# bh_carrier_0_alph.net
KiCad netlist of a schematic drawn in Altium Designer
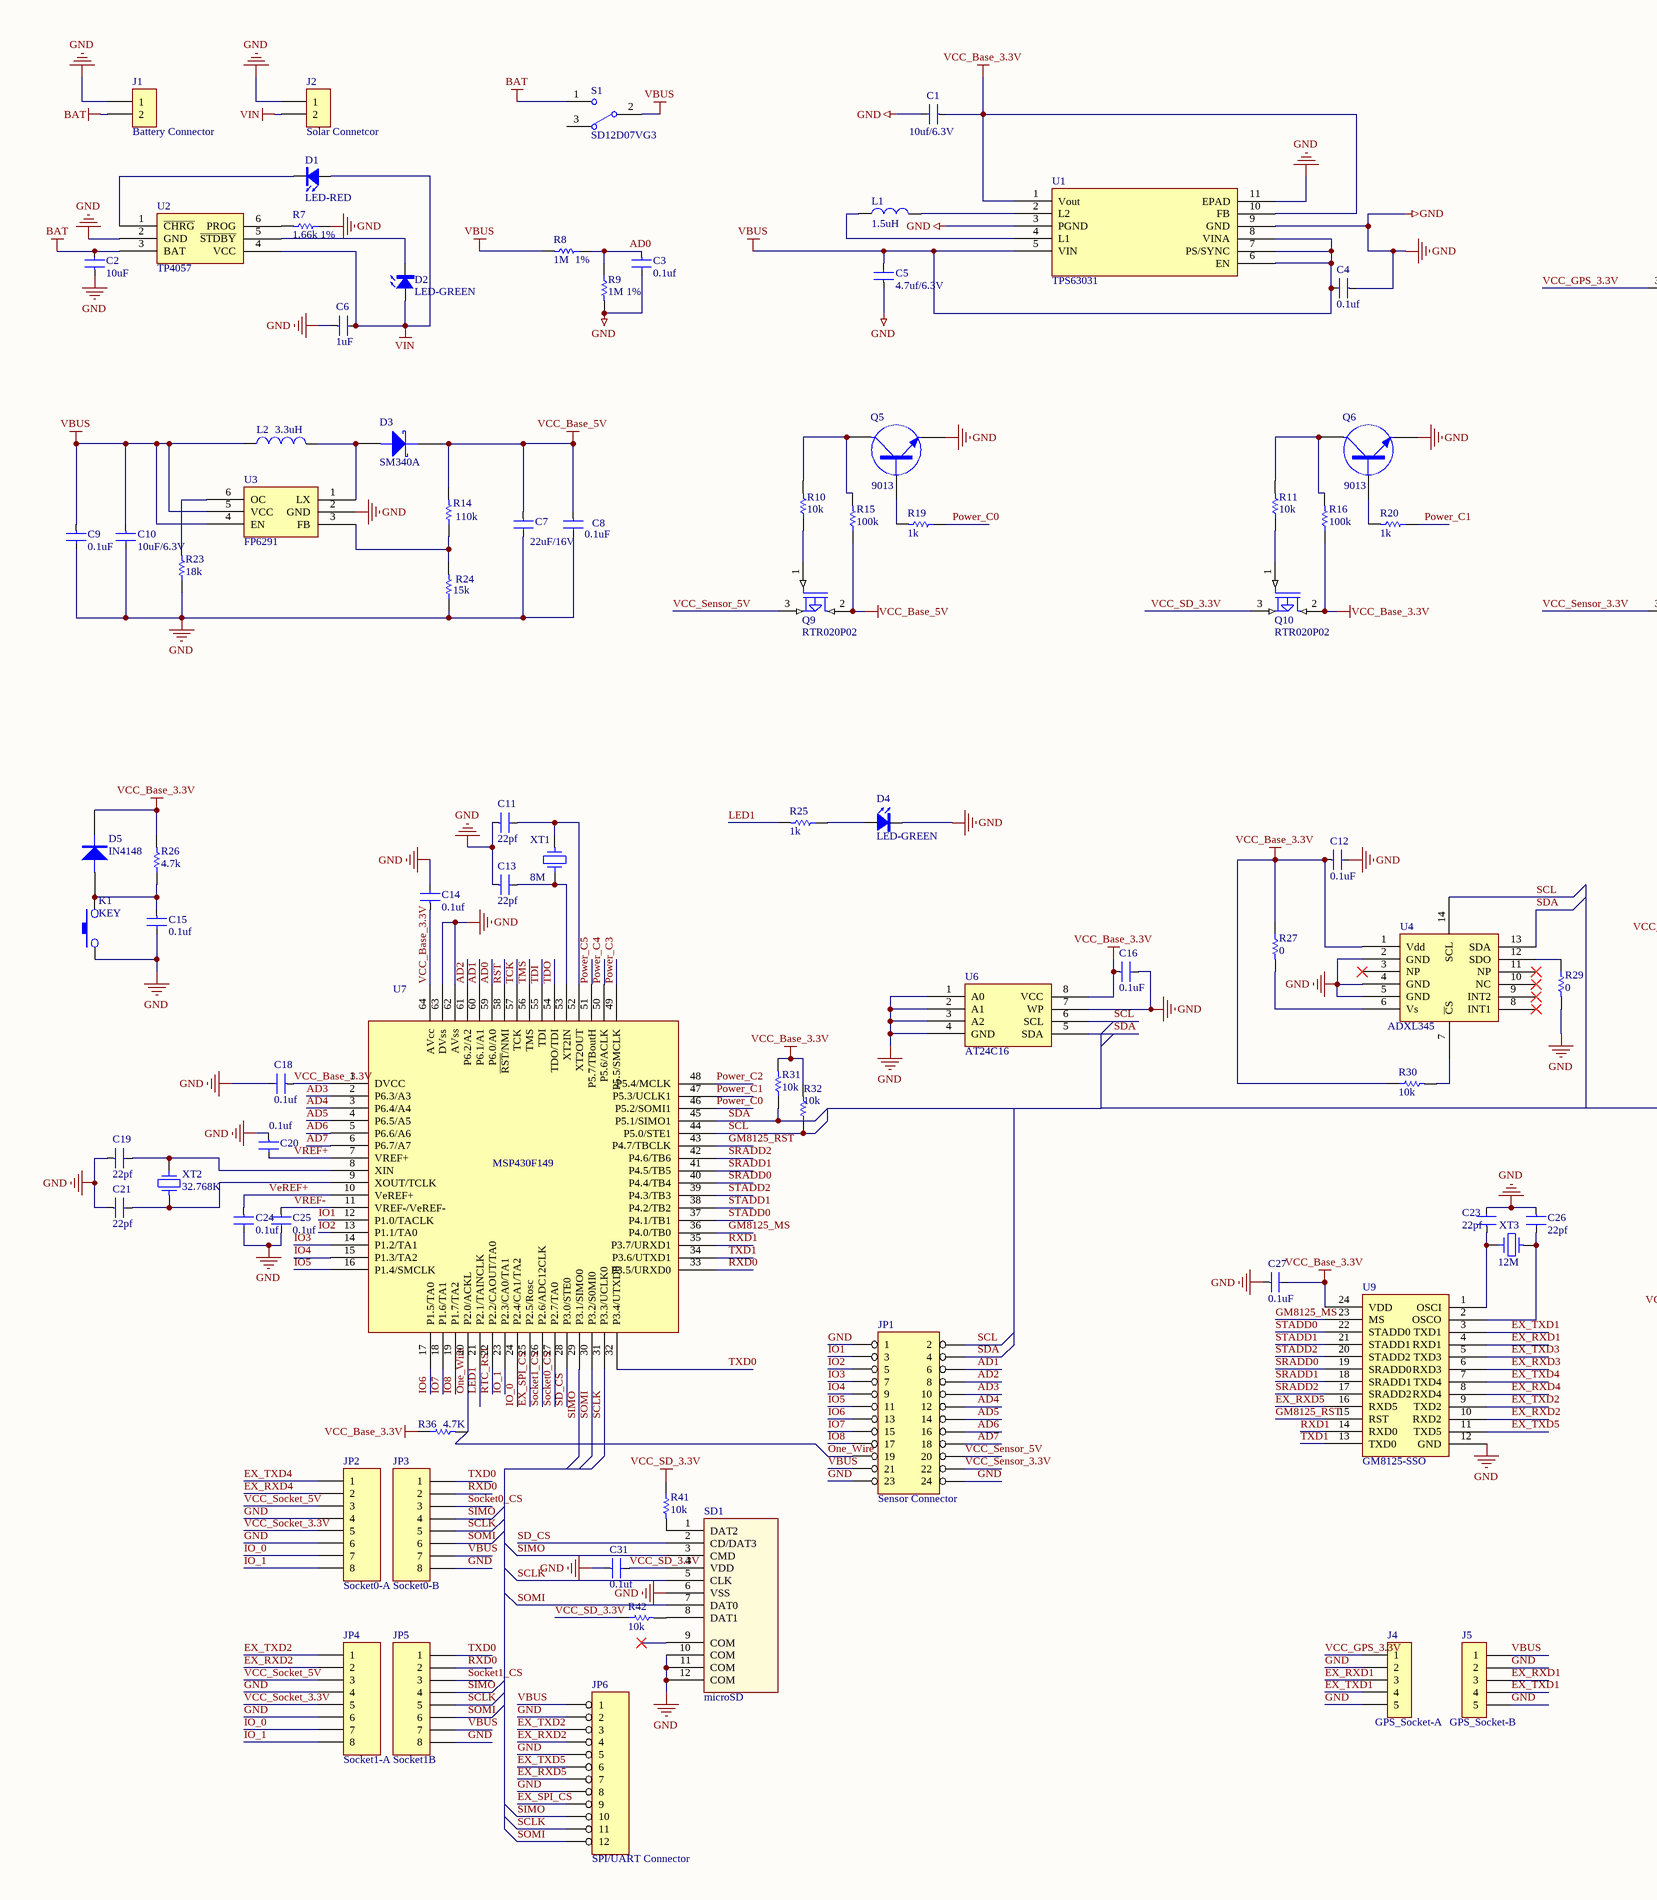
[diagram p0: bh_carrier_0_alph.SchDoc, left]
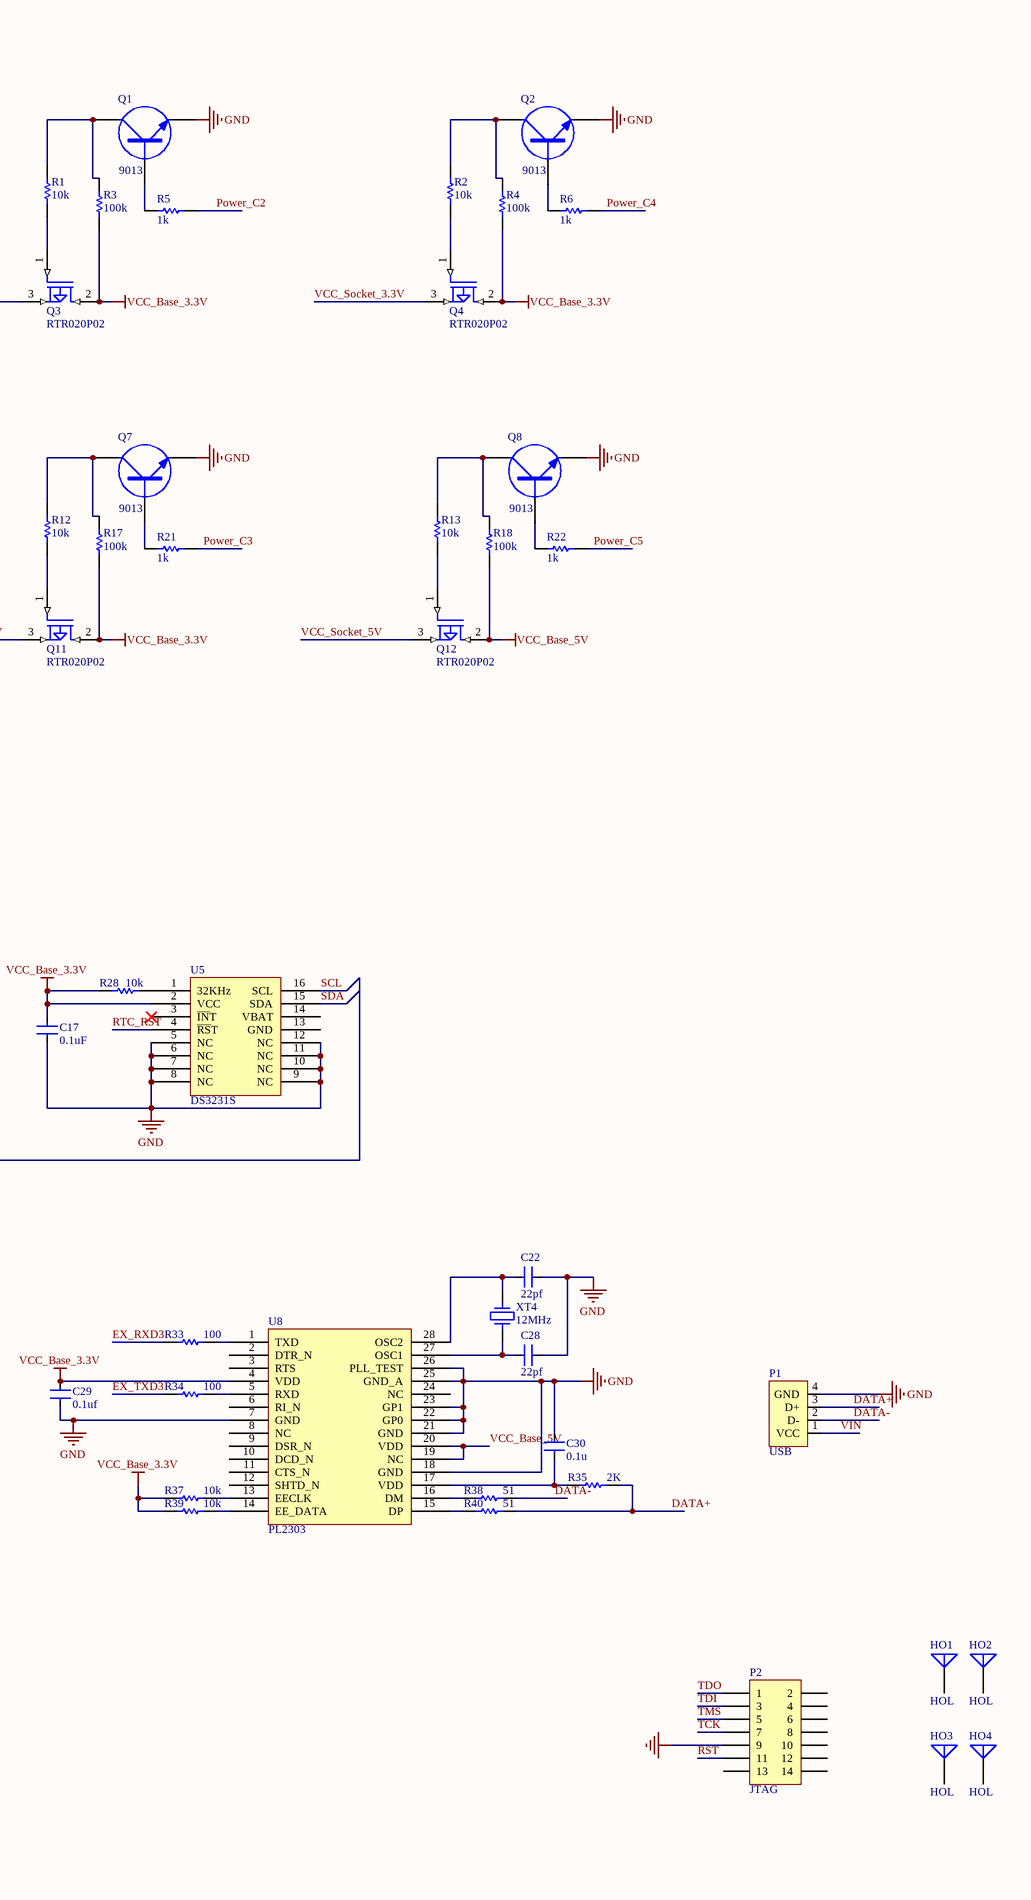
[diagram p1: bh_carrier_0_alph.SchDoc, right]

(export (version "E")
  (design (tool "Eeschema 10.0.6"))
  (components
    (comp (ref "C1")
      (value "10uf/6.3V")
      (footprint "C0603")
      (description "SMD-CAP")
      (libsource (lib "5D_USED_DEVICE") (part "CAP-SMD"))
    )
    (comp (ref "C2")
      (value "10uF")
      (footprint "C0603")
      (description "SMD-CAP")
      (libsource (lib "5D_DEVICE") (part "CAP-SMD"))
    )
    (comp (ref "C3")
      (value "0.1uf")
      (footprint "C0603")
      (description "SMD-CAP")
      (libsource (lib "5D_USED_DEVICE") (part "CAP-SMD"))
    )
    (comp (ref "C4")
      (value "0.1uf")
      (footprint "C0603")
      (description "SMD-CAP")
      (libsource (lib "5D_USED_DEVICE") (part "CAP-SMD"))
    )
    (comp (ref "C5")
      (value "4.7uf/6.3V")
      (footprint "C0603")
      (description "SMD-CAP")
      (libsource (lib "5D_USED_DEVICE") (part "CAP-SMD"))
    )
    (comp (ref "C6")
      (value "1uF")
      (footprint "C0603")
      (description "SMD-CAP")
      (libsource (lib "5D_DEVICE") (part "CAP-SMD"))
    )
    (comp (ref "C7")
      (value "22uF/16V")
      (footprint "C0603")
      (description "SMD-CAP")
      (libsource (lib "5D_DEVICE") (part "CAP-SMD"))
    )
    (comp (ref "C8")
      (value "0.1uF")
      (footprint "C0603")
      (description "SMD-CAP")
      (libsource (lib "5D_DEVICE") (part "CAP-SMD"))
    )
    (comp (ref "C9")
      (value "0.1uF")
      (footprint "C0603")
      (description "SMD-CAP")
      (libsource (lib "5D_DEVICE") (part "CAP-SMD"))
    )
    (comp (ref "C10")
      (value "10uF/6.3V")
      (footprint "C0603")
      (description "SMD-CAP")
      (libsource (lib "5D_DEVICE") (part "CAP-SMD"))
    )
    (comp (ref "C11")
      (value "22pf")
      (footprint "C0603")
      (description "SMD-CAP")
      (libsource (lib "5D_USED_DEVICE") (part "CAP-SMD"))
    )
    (comp (ref "C12")
      (value "0.1uF")
      (footprint "C0603")
      (description "SMD-CAP")
      (libsource (lib "5D_DEVICE") (part "CAP-SMD"))
    )
    (comp (ref "C13")
      (value "22pf")
      (footprint "C0603")
      (description "SMD-CAP")
      (libsource (lib "5D_USED_DEVICE") (part "CAP-SMD"))
    )
    (comp (ref "C14")
      (value "0.1uf")
      (footprint "C0603")
      (description "SMD-CAP")
      (libsource (lib "5D_USED_DEVICE") (part "CAP-SMD"))
    )
    (comp (ref "C15")
      (value "0.1uf")
      (footprint "C0603")
      (description "SMD-CAP")
      (libsource (lib "5D_USED_DEVICE") (part "CAP-SMD"))
    )
    (comp (ref "C16")
      (value "0.1uF")
      (footprint "C0603")
      (description "SMD-CAP")
      (libsource (lib "5D_DEVICE") (part "CAP-SMD"))
    )
    (comp (ref "C17")
      (value "0.1uF")
      (footprint "C0603")
      (description "SMD-CAP")
      (libsource (lib "5D_DEVICE") (part "CAP-SMD"))
    )
    (comp (ref "C18")
      (value "0.1uf")
      (footprint "C0603")
      (description "SMD-CAP")
      (libsource (lib "5D_USED_DEVICE") (part "CAP-SMD"))
    )
    (comp (ref "C19")
      (value "22pf")
      (footprint "C0603")
      (description "SMD-CAP")
      (libsource (lib "5D_USED_DEVICE") (part "CAP-SMD"))
    )
    (comp (ref "C20")
      (value "0.1uf")
      (footprint "C0603")
      (description "SMD-CAP")
      (libsource (lib "5D_USED_DEVICE") (part "CAP-SMD"))
    )
    (comp (ref "C21")
      (value "22pf")
      (footprint "C0603")
      (description "SMD-CAP")
      (libsource (lib "5D_USED_DEVICE") (part "CAP-SMD"))
    )
    (comp (ref "C22")
      (value "22pf")
      (footprint "C0603")
      (description "SMD-CAP")
      (libsource (lib "5D_USED_DEVICE") (part "CAP-SMD"))
    )
    (comp (ref "C23")
      (value "22pf")
      (footprint "C0603")
      (description "SMD-CAP")
      (libsource (lib "5D_USED_DEVICE") (part "CAP-SMD"))
    )
    (comp (ref "C24")
      (value "0.1uf")
      (footprint "C0603")
      (description "SMD-CAP")
      (libsource (lib "5D_USED_DEVICE") (part "CAP-SMD"))
    )
    (comp (ref "C25")
      (value "0.1uf")
      (footprint "C0603")
      (description "SMD-CAP")
      (libsource (lib "5D_USED_DEVICE") (part "CAP-SMD"))
    )
    (comp (ref "C26")
      (value "22pf")
      (footprint "C0603")
      (description "SMD-CAP")
      (libsource (lib "5D_USED_DEVICE") (part "CAP-SMD"))
    )
    (comp (ref "C27")
      (value "0.1uF")
      (footprint "C0603")
      (description "SMD-CAP")
      (libsource (lib "5D_DEVICE") (part "CAP-SMD"))
    )
    (comp (ref "C28")
      (value "22pf")
      (footprint "C0603")
      (description "SMD-CAP")
      (libsource (lib "5D_USED_DEVICE") (part "CAP-SMD"))
    )
    (comp (ref "C29")
      (value "0.1uf")
      (footprint "C0603")
      (description "SMD-CAP")
      (libsource (lib "5D_USED_DEVICE") (part "CAP-SMD"))
    )
    (comp (ref "C30")
      (value "0.1u")
      (footprint "C0603")
      (description "SMD-CAP")
      (libsource (lib "5D_USED_DEVICE") (part "CAP-SMD"))
    )
    (comp (ref "C31")
      (value "0.1uf")
      (footprint "C0603")
      (description "SMD-CAP")
      (libsource (lib "5D_USED_DEVICE") (part "CAP-SMD"))
    )
    (comp (ref "D1") (value "LED-RED") (footprint "D0805") (libsource (lib "") (part "LED_2")))
    (comp (ref "D2") (value "LED-GREEN") (footprint "D0805") (libsource (lib "") (part "LED_1")))
    (comp (ref "D3")
      (value "SM340A")
      (footprint "DO-214")
      (description "Schottky Diode")
      (libsource (lib "5D_DEVICE") (part "DIODE SCHOTTKY"))
    )
    (comp (ref "D4") (value "LED-GREEN") (footprint "D0805") (libsource (lib "5D_DEVICE") (part "LED")))
    (comp (ref "D5") (value "IN4148") (footprint "D1206") (libsource (lib "BH_DESIGN_DEVICE") (part "DIODE")))
    (comp (ref "HO1")
      (value "HOL")
      (footprint "HOLE1")
      (description "Generic Antenna")
      (fields (field (name "PUBLISHER") "Altium Limited"))
      (libsource (lib "Miscellaneous Devices") (part "Antenna"))
    )
    (comp (ref "HO2")
      (value "HOL")
      (footprint "HOLE1")
      (description "Generic Antenna")
      (fields (field (name "PUBLISHER") "Altium Limited"))
      (libsource (lib "Miscellaneous Devices") (part "Antenna"))
    )
    (comp (ref "HO3")
      (value "HOL")
      (footprint "HOLE1")
      (description "Generic Antenna")
      (fields (field (name "PUBLISHER") "Altium Limited"))
      (libsource (lib "Miscellaneous Devices") (part "Antenna"))
    )
    (comp (ref "HO4")
      (value "HOL")
      (footprint "HOLE1")
      (description "Generic Antenna")
      (fields (field (name "PUBLISHER") "Altium Limited"))
      (libsource (lib "Miscellaneous Devices") (part "Antenna"))
    )
    (comp (ref "J1")
      (value "Battery Connector")
      (footprint "SIP1X2X2.54")
      (description "Connector")
      (libsource (lib "5D_CONNECTOR") (part "SIP1X2"))
    )
    (comp (ref "J2")
      (value "Solar Connetcor")
      (footprint "SIP1X2X2.54")
      (description "Connector")
      (libsource (lib "5D_CONNECTOR") (part "SIP1X2"))
    )
    (comp (ref "J4")
      (value "GPS_Socket-A")
      (footprint "SIP1X5X2.54")
      (description "Connector")
      (libsource (lib "5D_CONNECTOR") (part "SIP1X5"))
    )
    (comp (ref "J5")
      (value "GPS_Socket-B")
      (footprint "SIP1X5X2.54")
      (description "Connector")
      (libsource (lib "") (part "SIP1X5_1"))
    )
    (comp (ref "JP1")
      (value "Sensor Connector")
      (footprint "SIP2X12X2.54")
      (libsource (lib "5D_CONNECTOR") (part "SIP2X12"))
    )
    (comp (ref "JP2")
      (value "Socket0-A")
      (footprint "SIP1x8x2.54")
      (description "8 Pin Header")
      (libsource (lib "") (part "SIP1X8_1"))
    )
    (comp (ref "JP3")
      (value "Socket0-B")
      (footprint "SIP1x8x2.54")
      (description "8 Pin Header")
      (libsource (lib "5D_CONNECTOR") (part "SIP1X8"))
    )
    (comp (ref "JP4")
      (value "Socket1-A")
      (footprint "SIP1x8x2.0")
      (description "8 Pin Header")
      (libsource (lib "") (part "SIP1X8_1"))
    )
    (comp (ref "JP5")
      (value "Socket1B")
      (footprint "SIP1x8x2.0")
      (description "8 Pin Header")
      (libsource (lib "5D_CONNECTOR") (part "SIP1X8"))
    )
    (comp (ref "JP6")
      (value "SPI/UART Connector")
      (footprint "SIP1x12x2.54")
      (description "12 Pin Header")
      (libsource (lib "5D_CONNECTOR") (part "SIP1X12"))
    )
    (comp (ref "K1") (value "KEY") (footprint "KEY_2Pin") (libsource (lib "5D_USED_DEVICE") (part "KEY")))
    (comp (ref "L1")
      (value "1.5uH")
      (footprint "LPS3010")
      (description "LPS3015-152")
      (libsource (lib "5D_DEVICE") (part "L1"))
    )
    (comp (ref "L2")
      (value "3.3uH")
      (footprint "L1206")
      (description "Inductor")
      (libsource (lib "5D_DEVICE") (part "INDUCTOR"))
    )
    (comp (ref "P1") (value "USB") (footprint "MicroUSB_four") (libsource (lib "5D_DEVICE") (part "USB")))
    (comp (ref "P2")
      (value "JTAG")
      (footprint "SIP2X7X2.54")
      (description "Header, 7-Pin, Dual row")
      (fields (field (name "PUBLISHER") "Altium Limited"))
      (libsource (lib "Miscellaneous Connectors") (part "Header 7X2"))
    )
    (comp (ref "Q1")
      (value "9013")
      (footprint "SOT-23")
      (description "NPN Transistor")
      (libsource (lib "5D_DEVICE") (part "NPN"))
    )
    (comp (ref "Q2")
      (value "9013")
      (footprint "SOT-23")
      (description "NPN Transistor")
      (libsource (lib "5D_DEVICE") (part "NPN"))
    )
    (comp (ref "Q3") (value "RTR020P02") (footprint "TSMT3") (libsource (lib "5D_DEVICE") (part "MOSFET P")))
    (comp (ref "Q4") (value "RTR020P02") (footprint "TSMT3") (libsource (lib "5D_DEVICE") (part "MOSFET P")))
    (comp (ref "Q5")
      (value "9013")
      (footprint "SOT-23")
      (description "NPN Transistor")
      (libsource (lib "5D_DEVICE") (part "NPN"))
    )
    (comp (ref "Q6")
      (value "9013")
      (footprint "SOT-23")
      (description "NPN Transistor")
      (libsource (lib "5D_DEVICE") (part "NPN"))
    )
    (comp (ref "Q7")
      (value "9013")
      (footprint "SOT-23")
      (description "NPN Transistor")
      (libsource (lib "5D_DEVICE") (part "NPN"))
    )
    (comp (ref "Q8")
      (value "9013")
      (footprint "SOT-23")
      (description "NPN Transistor")
      (libsource (lib "5D_DEVICE") (part "NPN"))
    )
    (comp (ref "Q9") (value "RTR020P02") (footprint "TSMT3") (libsource (lib "5D_DEVICE") (part "MOSFET P")))
    (comp (ref "Q10") (value "RTR020P02") (footprint "TSMT3") (libsource (lib "5D_DEVICE") (part "MOSFET P")))
    (comp (ref "Q11") (value "RTR020P02") (footprint "TSMT3") (libsource (lib "5D_DEVICE") (part "MOSFET P")))
    (comp (ref "Q12") (value "RTR020P02") (footprint "TSMT3") (libsource (lib "5D_DEVICE") (part "MOSFET P")))
    (comp (ref "R1")
      (value "10k")
      (footprint "R0603")
      (description "Resistor")
      (libsource (lib "5D_DEVICE") (part "RES"))
    )
    (comp (ref "R2")
      (value "10k")
      (footprint "R0603")
      (description "Resistor")
      (libsource (lib "5D_DEVICE") (part "RES"))
    )
    (comp (ref "R3")
      (value "100k")
      (footprint "R0603")
      (description "Resistor")
      (libsource (lib "5D_DEVICE") (part "RES"))
    )
    (comp (ref "R4")
      (value "100k")
      (footprint "R0603")
      (description "Resistor")
      (libsource (lib "5D_DEVICE") (part "RES"))
    )
    (comp (ref "R5")
      (value "1k")
      (footprint "R0603")
      (description "Resistor")
      (libsource (lib "5D_DEVICE") (part "RES"))
    )
    (comp (ref "R6")
      (value "1k")
      (footprint "R0603")
      (description "Resistor")
      (libsource (lib "5D_DEVICE") (part "RES"))
    )
    (comp (ref "R7")
      (value "1.66k 1%")
      (footprint "R0603")
      (description "Resistor")
      (libsource (lib "5D_DEVICE") (part "RES"))
    )
    (comp (ref "R8")
      (value "1M  1%")
      (footprint "R0603")
      (description "Resistor")
      (libsource (lib "5D_DEVICE") (part "RES"))
    )
    (comp (ref "R9")
      (value "1M 1%")
      (footprint "R0603")
      (description "Resistor")
      (libsource (lib "5D_DEVICE") (part "RES"))
    )
    (comp (ref "R10")
      (value "10k")
      (footprint "R0603")
      (description "Resistor")
      (libsource (lib "5D_DEVICE") (part "RES"))
    )
    (comp (ref "R11")
      (value "10k")
      (footprint "R0603")
      (description "Resistor")
      (libsource (lib "5D_DEVICE") (part "RES"))
    )
    (comp (ref "R12")
      (value "10k")
      (footprint "R0603")
      (description "Resistor")
      (libsource (lib "5D_DEVICE") (part "RES"))
    )
    (comp (ref "R13")
      (value "10k")
      (footprint "R0603")
      (description "Resistor")
      (libsource (lib "5D_DEVICE") (part "RES"))
    )
    (comp (ref "R14")
      (value "110k")
      (footprint "R0603")
      (description "Resistor")
      (libsource (lib "5D_DEVICE") (part "RES"))
    )
    (comp (ref "R15")
      (value "100k")
      (footprint "R0603")
      (description "Resistor")
      (libsource (lib "5D_DEVICE") (part "RES"))
    )
    (comp (ref "R16")
      (value "100k")
      (footprint "R0603")
      (description "Resistor")
      (libsource (lib "5D_DEVICE") (part "RES"))
    )
    (comp (ref "R17")
      (value "100k")
      (footprint "R0603")
      (description "Resistor")
      (libsource (lib "5D_DEVICE") (part "RES"))
    )
    (comp (ref "R18")
      (value "100k")
      (footprint "R0603")
      (description "Resistor")
      (libsource (lib "5D_DEVICE") (part "RES"))
    )
    (comp (ref "R19")
      (value "1k")
      (footprint "R0603")
      (description "Resistor")
      (libsource (lib "5D_DEVICE") (part "RES"))
    )
    (comp (ref "R20")
      (value "1k")
      (footprint "R0603")
      (description "Resistor")
      (libsource (lib "5D_DEVICE") (part "RES"))
    )
    (comp (ref "R21")
      (value "1k")
      (footprint "R0603")
      (description "Resistor")
      (libsource (lib "5D_DEVICE") (part "RES"))
    )
    (comp (ref "R22")
      (value "1k")
      (footprint "R0603")
      (description "Resistor")
      (libsource (lib "5D_DEVICE") (part "RES"))
    )
    (comp (ref "R23")
      (value "18k")
      (footprint "R0603")
      (description "Resistor")
      (libsource (lib "5D_DEVICE") (part "RES"))
    )
    (comp (ref "R24")
      (value "15k")
      (footprint "R0603")
      (description "Resistor")
      (libsource (lib "5D_DEVICE") (part "RES"))
    )
    (comp (ref "R25")
      (value "1k")
      (footprint "R0603")
      (description "Resistor")
      (libsource (lib "5D_DEVICE") (part "RES"))
    )
    (comp (ref "R26")
      (value "4.7k")
      (footprint "R0603")
      (description "Resistor")
      (libsource (lib "5D_DEVICE") (part "RES"))
    )
    (comp (ref "R27")
      (value "0")
      (footprint "R0603")
      (description "Resistor")
      (libsource (lib "5D_DEVICE") (part "RES"))
    )
    (comp (ref "R28")
      (value "10k")
      (footprint "R0603")
      (description "Resistor")
      (libsource (lib "5D_DEVICE") (part "RES"))
    )
    (comp (ref "R29")
      (value "0")
      (footprint "R0603")
      (description "Resistor")
      (libsource (lib "5D_DEVICE") (part "RES"))
    )
    (comp (ref "R30")
      (value "10k")
      (footprint "R0603")
      (description "Resistor")
      (libsource (lib "5D_DEVICE") (part "RES"))
    )
    (comp (ref "R31")
      (value "10k")
      (footprint "R0603")
      (description "Resistor")
      (libsource (lib "5D_DEVICE") (part "RES"))
    )
    (comp (ref "R32")
      (value "10k")
      (footprint "R0603")
      (description "Resistor")
      (libsource (lib "5D_DEVICE") (part "RES"))
    )
    (comp (ref "R33")
      (value "100")
      (footprint "R0603")
      (description "Resistor")
      (libsource (lib "5D_DEVICE") (part "RES"))
    )
    (comp (ref "R34")
      (value "100")
      (footprint "R0603")
      (description "Resistor")
      (libsource (lib "5D_DEVICE") (part "RES"))
    )
    (comp (ref "R35")
      (value "2K")
      (footprint "R0603")
      (description "Resistor")
      (fields (field (name "Comment") "2k"))
      (libsource (lib "5D_DEVICE") (part "RES"))
    )
    (comp (ref "R36")
      (value "4.7K")
      (footprint "R0603")
      (description "Resistor")
      (libsource (lib "5D_DEVICE") (part "RES"))
    )
    (comp (ref "R37")
      (value "10k")
      (footprint "R0603")
      (description "Resistor")
      (libsource (lib "5D_DEVICE") (part "RES"))
    )
    (comp (ref "R38")
      (value "51")
      (footprint "R0603")
      (description "Resistor")
      (libsource (lib "5D_DEVICE") (part "RES"))
    )
    (comp (ref "R39")
      (value "10k")
      (footprint "R0603")
      (description "Resistor")
      (libsource (lib "5D_DEVICE") (part "RES"))
    )
    (comp (ref "R40")
      (value "51")
      (footprint "R0603")
      (description "Resistor")
      (libsource (lib "5D_DEVICE") (part "RES"))
    )
    (comp (ref "R41")
      (value "10k")
      (footprint "R0603")
      (description "Resistor")
      (libsource (lib "5D_DEVICE") (part "RES"))
    )
    (comp (ref "R42")
      (value "10k")
      (footprint "R0603")
      (description "Resistor")
      (libsource (lib "5D_DEVICE") (part "RES"))
    )
    (comp (ref "S1")
      (value "SD12D07VG3")
      (footprint "SW-1-2")
      (fields (field (name "PUBLISHER") "Altium Limited"))
      (libsource (lib "Miscellaneous Devices") (part "SW-SPDT"))
    )
    (comp (ref "SD1") (value "microSD") (footprint "TF_CARD") (libsource (lib "tlib") (part "microSD")))
    (comp (ref "U1") (value "TPS63031") (footprint "QFN-10") (libsource (lib "5D_IC") (part "TPS63031_2")))
    (comp (ref "U2") (value "TP4057") (footprint "SOT23-6") (libsource (lib "5D_DEVICE") (part "PT4057")))
    (comp (ref "U3") (value "FP6291") (footprint "SOT23-6") (libsource (lib "5D_IC") (part "FP6291")))
    (comp (ref "U4") (value "ADXL345") (footprint "LGA-CC-14-1") (libsource (lib "5D_IC") (part "ADXL345")))
    (comp (ref "U5") (value "DS3231S") (footprint "SO-16") (libsource (lib "5D_IC") (part "DS3231")))
    (comp (ref "U6") (value "AT24C16") (footprint "SO-8") (libsource (lib "5D_IC") (part "AT24C16")))
    (comp (ref "U7")
      (value "MSP430F149")
      (footprint "LQFP64_M")
      (libsource (lib "Schlib1") (part "MSP430F149"))
    )
    (comp (ref "U8") (value "PL2303") (footprint "SOP28") (libsource (lib "Schlib1") (part "PL2303")))
    (comp (ref "U9") (value "GM8125-SSO") (footprint "SOP-24") (libsource (lib "5D_IC") (part "GM8125")))
    (comp (ref "XT1")
      (value "8M")
      (footprint "HC-49S")
      (description "晶振")
      (libsource (lib "5D_USED_DEVICE") (part "XT"))
    )
    (comp (ref "XT2")
      (value "32.768K")
      (footprint "AT308")
      (description "晶振")
      (libsource (lib "5D_USED_DEVICE") (part "XT"))
    )
    (comp (ref "XT3")
      (value "12M")
      (footprint "HC-49S")
      (description "晶振")
      (libsource (lib "5D_USED_DEVICE") (part "XT"))
    )
    (comp (ref "XT4")
      (value "12MHz")
      (footprint "HC-49S")
      (description "晶振")
      (libsource (lib "5D_USED_DEVICE") (part "XT"))
    )
  )
  (nets
    (net (code "1") (name "/AD0") (class "Default")
      (node (ref "C3") (pin "1") (pinfunction "1_1") (pintype "passive"))
      (node (ref "R8") (pin "1") (pinfunction "1_1") (pintype "passive"))
      (node (ref "R9") (pin "1") (pinfunction "1_1") (pintype "passive"))
      (node (ref "U7") (pin "59") (pinfunction "P6.0/A0_59") (pintype "passive"))
    )
    (net (code "2") (name "/AD1") (class "Default")
      (node (ref "JP1") (pin "6") (pinfunction "6_6") (pintype "passive"))
      (node (ref "U7") (pin "60") (pinfunction "P6.1/A1_60") (pintype "passive"))
    )
    (net (code "3") (name "/AD2") (class "Default")
      (node (ref "JP1") (pin "8") (pinfunction "8_8") (pintype "passive"))
      (node (ref "U7") (pin "61") (pinfunction "P6.2/A2_61") (pintype "passive"))
    )
    (net (code "4") (name "/AD3") (class "Default")
      (node (ref "JP1") (pin "10") (pinfunction "10_10") (pintype "passive"))
      (node (ref "U7") (pin "2") (pinfunction "P6.3/A3_2") (pintype "passive"))
    )
    (net (code "5") (name "/AD4") (class "Default")
      (node (ref "JP1") (pin "12") (pinfunction "12_12") (pintype "passive"))
      (node (ref "U7") (pin "3") (pinfunction "P6.4/A4_3") (pintype "passive"))
    )
    (net (code "6") (name "/AD5") (class "Default")
      (node (ref "JP1") (pin "14") (pinfunction "14_14") (pintype "passive"))
      (node (ref "U7") (pin "4") (pinfunction "P6.5/A5_4") (pintype "passive"))
    )
    (net (code "7") (name "/AD6") (class "Default")
      (node (ref "JP1") (pin "16") (pinfunction "16_16") (pintype "passive"))
      (node (ref "U7") (pin "5") (pinfunction "P6.6/A6_5") (pintype "passive"))
    )
    (net (code "8") (name "/AD7") (class "Default")
      (node (ref "JP1") (pin "18") (pinfunction "18_18") (pintype "passive"))
      (node (ref "U7") (pin "6") (pinfunction "P6.7/A7_6") (pintype "passive"))
    )
    (net (code "9") (name "/DATA+") (class "Default")
      (node (ref "P1") (pin "3") (pinfunction "D+_3") (pintype "passive"))
      (node (ref "R35") (pin "1") (pinfunction "1_1") (pintype "passive"))
      (node (ref "R40") (pin "1") (pinfunction "1_1") (pintype "passive"))
    )
    (net (code "10") (name "/DATA-") (class "Default")
      (node (ref "P1") (pin "2") (pinfunction "D-_2") (pintype "passive"))
      (node (ref "R38") (pin "1") (pinfunction "1_1") (pintype "passive"))
    )
    (net (code "11") (name "/EX_RXD1") (class "Default")
      (node (ref "J4") (pin "3") (pinfunction "3_3") (pintype "passive"))
      (node (ref "J5") (pin "3") (pinfunction "3_3") (pintype "passive"))
      (node (ref "U9") (pin "4") (pinfunction "RXD1_4") (pintype "passive"))
    )
    (net (code "12") (name "/EX_RXD2") (class "Default")
      (node (ref "JP4") (pin "2") (pinfunction "2_2") (pintype "passive"))
      (node (ref "JP6") (pin "4") (pinfunction "4_4") (pintype "passive"))
      (node (ref "U9") (pin "10") (pinfunction "RXD2_10") (pintype "passive"))
    )
    (net (code "13") (name "/EX_RXD3") (class "Default")
      (node (ref "R33") (pin "2") (pinfunction "2_2") (pintype "passive"))
      (node (ref "U9") (pin "6") (pinfunction "RXD3_6") (pintype "passive"))
    )
    (net (code "14") (name "/EX_RXD4") (class "Default")
      (node (ref "JP2") (pin "2") (pinfunction "2_2") (pintype "passive"))
      (node (ref "U9") (pin "8") (pinfunction "RXD4_8") (pintype "passive"))
    )
    (net (code "15") (name "/EX_RXD5") (class "Default")
      (node (ref "JP6") (pin "7") (pinfunction "7_7") (pintype "passive"))
      (node (ref "U9") (pin "16") (pinfunction "RXD5_16") (pintype "passive"))
    )
    (net (code "16") (name "/EX_SPI_CS") (class "Default")
      (node (ref "JP6") (pin "9") (pinfunction "9_9") (pintype "passive"))
      (node (ref "U7") (pin "25") (pinfunction "P2.5/Rosc_25") (pintype "passive"))
    )
    (net (code "17") (name "/EX_TXD1") (class "Default")
      (node (ref "J4") (pin "4") (pinfunction "4_4") (pintype "passive"))
      (node (ref "J5") (pin "4") (pinfunction "4_4") (pintype "passive"))
      (node (ref "U9") (pin "3") (pinfunction "TXD1_3") (pintype "passive"))
    )
    (net (code "18") (name "/EX_TXD2") (class "Default")
      (node (ref "JP4") (pin "1") (pinfunction "1_1") (pintype "passive"))
      (node (ref "JP6") (pin "3") (pinfunction "3_3") (pintype "passive"))
      (node (ref "U9") (pin "9") (pinfunction "TXD2_9") (pintype "passive"))
    )
    (net (code "19") (name "/EX_TXD3") (class "Default")
      (node (ref "R34") (pin "2") (pinfunction "2_2") (pintype "passive"))
      (node (ref "U9") (pin "5") (pinfunction "TXD3_5") (pintype "passive"))
    )
    (net (code "20") (name "/EX_TXD4") (class "Default")
      (node (ref "JP2") (pin "1") (pinfunction "1_1") (pintype "passive"))
      (node (ref "U9") (pin "7") (pinfunction "TXD4_7") (pintype "passive"))
    )
    (net (code "21") (name "/EX_TXD5") (class "Default")
      (node (ref "JP6") (pin "6") (pinfunction "6_6") (pintype "passive"))
      (node (ref "U9") (pin "11") (pinfunction "TXD5_11") (pintype "passive"))
    )
    (net (code "22") (name "/GM8125_MS") (class "Default")
      (node (ref "U7") (pin "36") (pinfunction "P4.0/TB0_36") (pintype "passive"))
      (node (ref "U9") (pin "23") (pinfunction "MS_23") (pintype "passive"))
    )
    (net (code "23") (name "/GM8125_RST") (class "Default")
      (node (ref "U7") (pin "43") (pinfunction "P4.7/TBCLK_43") (pintype "passive"))
      (node (ref "U9") (pin "15") (pinfunction "RST_15") (pintype "passive"))
    )
    (net (code "24") (name "/IO1") (class "Default")
      (node (ref "JP1") (pin "3") (pinfunction "3_3") (pintype "passive"))
      (node (ref "U7") (pin "12") (pinfunction "P1.0/TACLK_12") (pintype "passive"))
    )
    (net (code "25") (name "/IO2") (class "Default")
      (node (ref "JP1") (pin "5") (pinfunction "5_5") (pintype "passive"))
      (node (ref "U7") (pin "13") (pinfunction "P1.1/TA0_13") (pintype "passive"))
    )
    (net (code "26") (name "/IO3") (class "Default")
      (node (ref "JP1") (pin "7") (pinfunction "7_7") (pintype "passive"))
      (node (ref "U7") (pin "14") (pinfunction "P1.2/TA1_14") (pintype "passive"))
    )
    (net (code "27") (name "/IO4") (class "Default")
      (node (ref "JP1") (pin "9") (pinfunction "9_9") (pintype "passive"))
      (node (ref "U7") (pin "15") (pinfunction "P1.3/TA2_15") (pintype "passive"))
    )
    (net (code "28") (name "/IO5") (class "Default")
      (node (ref "JP1") (pin "11") (pinfunction "11_11") (pintype "passive"))
      (node (ref "U7") (pin "16") (pinfunction "P1.4/SMCLK_16") (pintype "passive"))
    )
    (net (code "29") (name "/IO6") (class "Default")
      (node (ref "JP1") (pin "13") (pinfunction "13_13") (pintype "passive"))
      (node (ref "U7") (pin "17") (pinfunction "P1.5/TA0_17") (pintype "passive"))
    )
    (net (code "30") (name "/IO7") (class "Default")
      (node (ref "JP1") (pin "15") (pinfunction "15_15") (pintype "passive"))
      (node (ref "U7") (pin "18") (pinfunction "P1.6/TA1_18") (pintype "passive"))
    )
    (net (code "31") (name "/IO8") (class "Default")
      (node (ref "JP1") (pin "17") (pinfunction "17_17") (pintype "passive"))
      (node (ref "U7") (pin "19") (pinfunction "P1.7/TA2_19") (pintype "passive"))
    )
    (net (code "32") (name "/IO_0") (class "Default")
      (node (ref "JP2") (pin "7") (pinfunction "7_7") (pintype "passive"))
      (node (ref "JP4") (pin "7") (pinfunction "7_7") (pintype "passive"))
      (node (ref "U7") (pin "24") (pinfunction "P2.4/CA1/TA2_24") (pintype "passive"))
    )
    (net (code "33") (name "/IO_1") (class "Default")
      (node (ref "JP2") (pin "8") (pinfunction "8_8") (pintype "passive"))
      (node (ref "JP4") (pin "8") (pinfunction "8_8") (pintype "passive"))
      (node (ref "U7") (pin "23") (pinfunction "P2.3/CA0/TA1_23") (pintype "passive"))
    )
    (net (code "34") (name "/LED1") (class "Default")
      (node (ref "R25") (pin "2") (pinfunction "2_2") (pintype "passive"))
      (node (ref "U7") (pin "21") (pinfunction "P2.1/TAINCLK_21") (pintype "passive"))
    )
    (net (code "35") (name "/One_Wire") (class "Default")
      (node (ref "JP1") (pin "19") (pinfunction "19_19") (pintype "passive"))
      (node (ref "R36") (pin "2") (pinfunction "2_2") (pintype "passive"))
      (node (ref "U7") (pin "20") (pinfunction "P2.0/ACKL_20") (pintype "passive"))
    )
    (net (code "36") (name "/Power_C0") (class "Default")
      (node (ref "R19") (pin "1") (pinfunction "1_1") (pintype "passive"))
      (node (ref "U7") (pin "46") (pinfunction "P5.2/SOMI1_46") (pintype "passive"))
    )
    (net (code "37") (name "/Power_C1") (class "Default")
      (node (ref "R20") (pin "1") (pinfunction "1_1") (pintype "passive"))
      (node (ref "U7") (pin "47") (pinfunction "P5.3/UCLK1_47") (pintype "passive"))
    )
    (net (code "38") (name "/Power_C2") (class "Default")
      (node (ref "R5") (pin "1") (pinfunction "1_1") (pintype "passive"))
      (node (ref "U7") (pin "48") (pinfunction "P5.4/MCLK_48") (pintype "passive"))
    )
    (net (code "39") (name "/Power_C3") (class "Default")
      (node (ref "R21") (pin "1") (pinfunction "1_1") (pintype "passive"))
      (node (ref "U7") (pin "49") (pinfunction "P5.5/SMCLK_49") (pintype "passive"))
    )
    (net (code "40") (name "/Power_C4") (class "Default")
      (node (ref "R6") (pin "1") (pinfunction "1_1") (pintype "passive"))
      (node (ref "U7") (pin "50") (pinfunction "P5.6/ACLK_50") (pintype "passive"))
    )
    (net (code "41") (name "/Power_C5") (class "Default")
      (node (ref "R22") (pin "1") (pinfunction "1_1") (pintype "passive"))
      (node (ref "U7") (pin "51") (pinfunction "P5.7/TBoutH_51") (pintype "passive"))
    )
    (net (code "42") (name "/RST") (class "Default")
      (node (ref "P2") (pin "11") (pinfunction "11_11") (pintype "passive"))
      (node (ref "U7") (pin "58") (pinfunction "~{RST}/NMI_58") (pintype "passive"))
    )
    (net (code "43") (name "/RTC_RST") (class "Default")
      (node (ref "U5") (pin "4") (pinfunction "~{RS}T_4") (pintype "passive"))
      (node (ref "U7") (pin "22") (pinfunction "P2.2/CAOUT/TA0_22") (pintype "passive"))
    )
    (net (code "44") (name "/RXD0") (class "Default")
      (node (ref "JP3") (pin "2") (pinfunction "2_2") (pintype "passive"))
      (node (ref "JP5") (pin "2") (pinfunction "2_2") (pintype "passive"))
      (node (ref "U7") (pin "33") (pinfunction "P3.5/URXD0_33") (pintype "passive"))
    )
    (net (code "45") (name "/RXD1") (class "Default")
      (node (ref "U7") (pin "35") (pinfunction "P3.7/URXD1_35") (pintype "passive"))
      (node (ref "U9") (pin "14") (pinfunction "RXD0_14") (pintype "passive"))
    )
    (net (code "46") (name "/SCL") (class "Default")
      (node (ref "JP1") (pin "2") (pinfunction "2_2") (pintype "passive"))
      (node (ref "R32") (pin "1") (pinfunction "1_1") (pintype "passive"))
      (node (ref "U4") (pin "14") (pinfunction "SCL_14") (pintype "passive"))
      (node (ref "U5") (pin "16") (pinfunction "SCL_16") (pintype "passive"))
      (node (ref "U6") (pin "6") (pinfunction "SCL_6") (pintype "passive"))
      (node (ref "U7") (pin "44") (pinfunction "P5.0/STE1_44") (pintype "passive"))
    )
    (net (code "47") (name "/SCLK") (class "Default")
      (node (ref "JP3") (pin "5") (pinfunction "5_5") (pintype "passive"))
      (node (ref "JP5") (pin "5") (pinfunction "5_5") (pintype "passive"))
      (node (ref "JP6") (pin "11") (pinfunction "11_11") (pintype "passive"))
      (node (ref "SD1") (pin "5") (pinfunction "CLK_5") (pintype "passive"))
      (node (ref "U7") (pin "31") (pinfunction "P3.3/UCLK0_31") (pintype "passive"))
    )
    (net (code "48") (name "/SDA") (class "Default")
      (node (ref "JP1") (pin "4") (pinfunction "4_4") (pintype "passive"))
      (node (ref "R31") (pin "1") (pinfunction "1_1") (pintype "passive"))
      (node (ref "U4") (pin "13") (pinfunction "SDA_13") (pintype "passive"))
      (node (ref "U5") (pin "15") (pinfunction "SDA_15") (pintype "passive"))
      (node (ref "U6") (pin "5") (pinfunction "SDA_5") (pintype "passive"))
      (node (ref "U7") (pin "45") (pinfunction "P5.1/SIMO1_45") (pintype "passive"))
    )
    (net (code "49") (name "/SD_CS") (class "Default")
      (node (ref "SD1") (pin "2") (pinfunction "CD/DAT3_2") (pintype "passive"))
      (node (ref "U7") (pin "28") (pinfunction "P3.0/STE0_28") (pintype "passive"))
    )
    (net (code "50") (name "/SIMO") (class "Default")
      (node (ref "JP3") (pin "4") (pinfunction "4_4") (pintype "passive"))
      (node (ref "JP5") (pin "4") (pinfunction "4_4") (pintype "passive"))
      (node (ref "JP6") (pin "10") (pinfunction "10_10") (pintype "passive"))
      (node (ref "SD1") (pin "3") (pinfunction "CMD_3") (pintype "passive"))
      (node (ref "U7") (pin "29") (pinfunction "P3.1/SIMO0_29") (pintype "passive"))
    )
    (net (code "51") (name "/SOMI") (class "Default")
      (node (ref "JP3") (pin "6") (pinfunction "6_6") (pintype "passive"))
      (node (ref "JP5") (pin "6") (pinfunction "6_6") (pintype "passive"))
      (node (ref "JP6") (pin "12") (pinfunction "12_12") (pintype "passive"))
      (node (ref "SD1") (pin "7") (pinfunction "DAT0_7") (pintype "passive"))
      (node (ref "U7") (pin "30") (pinfunction "P3.2/S0MI0_30") (pintype "passive"))
    )
    (net (code "52") (name "/SRADD0") (class "Default")
      (node (ref "U7") (pin "40") (pinfunction "P4.4/TB4_40") (pintype "passive"))
      (node (ref "U9") (pin "19") (pinfunction "SRADD0_19") (pintype "passive"))
    )
    (net (code "53") (name "/SRADD1") (class "Default")
      (node (ref "U7") (pin "41") (pinfunction "P4.5/TB5_41") (pintype "passive"))
      (node (ref "U9") (pin "18") (pinfunction "SRADD1_18") (pintype "passive"))
    )
    (net (code "54") (name "/SRADD2") (class "Default")
      (node (ref "U7") (pin "42") (pinfunction "P4.6/TB6_42") (pintype "passive"))
      (node (ref "U9") (pin "17") (pinfunction "SRADD2_17") (pintype "passive"))
    )
    (net (code "55") (name "/STADD0") (class "Default")
      (node (ref "U7") (pin "37") (pinfunction "P4.1/TB1_37") (pintype "passive"))
      (node (ref "U9") (pin "22") (pinfunction "STADD0_22") (pintype "passive"))
    )
    (net (code "56") (name "/STADD1") (class "Default")
      (node (ref "U7") (pin "38") (pinfunction "P4.2/TB2_38") (pintype "passive"))
      (node (ref "U9") (pin "21") (pinfunction "STADD1_21") (pintype "passive"))
    )
    (net (code "57") (name "/STADD2") (class "Default")
      (node (ref "U7") (pin "39") (pinfunction "P4.3/TB3_39") (pintype "passive"))
      (node (ref "U9") (pin "20") (pinfunction "STADD2_20") (pintype "passive"))
    )
    (net (code "58") (name "/Socket0_CS") (class "Default")
      (node (ref "JP3") (pin "3") (pinfunction "3_3") (pintype "passive"))
      (node (ref "U7") (pin "27") (pinfunction "P2.7/TA0_27") (pintype "passive"))
    )
    (net (code "59") (name "/Socket1_CS") (class "Default")
      (node (ref "JP5") (pin "3") (pinfunction "3_3") (pintype "passive"))
      (node (ref "U7") (pin "26") (pinfunction "P2.6/ADC12CLK_26") (pintype "passive"))
    )
    (net (code "60") (name "/TCK") (class "Default")
      (node (ref "P2") (pin "7") (pinfunction "7_7") (pintype "passive"))
      (node (ref "U7") (pin "57") (pinfunction "TCK_57") (pintype "passive"))
    )
    (net (code "61") (name "/TDI") (class "Default")
      (node (ref "P2") (pin "3") (pinfunction "3_3") (pintype "passive"))
      (node (ref "U7") (pin "55") (pinfunction "TDI_55") (pintype "passive"))
    )
    (net (code "62") (name "/TDO") (class "Default")
      (node (ref "P2") (pin "1") (pinfunction "1_1") (pintype "passive"))
      (node (ref "U7") (pin "54") (pinfunction "TDO/TDI_54") (pintype "passive"))
    )
    (net (code "63") (name "/TMS") (class "Default")
      (node (ref "P2") (pin "5") (pinfunction "5_5") (pintype "passive"))
      (node (ref "U7") (pin "56") (pinfunction "TMS_56") (pintype "passive"))
    )
    (net (code "64") (name "/TXD0") (class "Default")
      (node (ref "JP3") (pin "1") (pinfunction "1_1") (pintype "passive"))
      (node (ref "JP5") (pin "1") (pinfunction "1_1") (pintype "passive"))
      (node (ref "U7") (pin "32") (pinfunction "P3.4/UTXD0_32") (pintype "passive"))
    )
    (net (code "65") (name "/TXD1") (class "Default")
      (node (ref "U7") (pin "34") (pinfunction "P3.6/UTXD1_34") (pintype "passive"))
      (node (ref "U9") (pin "13") (pinfunction "TXD0_13") (pintype "passive"))
    )
    (net (code "66") (name "/VCC_GPS_3.3V") (class "Default")
      (node (ref "J4") (pin "1") (pinfunction "1_1") (pintype "passive"))
      (node (ref "Q3") (pin "3") (pinfunction "S_3") (pintype "input"))
    )
    (net (code "67") (name "/VCC_Sensor_3.3V") (class "Default")
      (node (ref "JP1") (pin "22") (pinfunction "22_22") (pintype "passive"))
      (node (ref "Q11") (pin "3") (pinfunction "S_3") (pintype "input"))
    )
    (net (code "68") (name "/VCC_Sensor_5V") (class "Default")
      (node (ref "JP1") (pin "20") (pinfunction "20_20") (pintype "passive"))
      (node (ref "Q9") (pin "3") (pinfunction "S_3") (pintype "input"))
    )
    (net (code "69") (name "/VCC_Socket_3.3V") (class "Default")
      (node (ref "JP2") (pin "5") (pinfunction "5_5") (pintype "passive"))
      (node (ref "JP4") (pin "5") (pinfunction "5_5") (pintype "passive"))
      (node (ref "Q4") (pin "3") (pinfunction "S_3") (pintype "input"))
    )
    (net (code "70") (name "/VCC_Socket_5V") (class "Default")
      (node (ref "JP2") (pin "3") (pinfunction "3_3") (pintype "passive"))
      (node (ref "JP4") (pin "3") (pinfunction "3_3") (pintype "passive"))
      (node (ref "Q12") (pin "3") (pinfunction "S_3") (pintype "input"))
    )
    (net (code "71") (name "/VREF+") (class "Default")
      (node (ref "C20") (pin "2") (pinfunction "2_2") (pintype "passive"))
      (node (ref "U7") (pin "7") (pinfunction "VREF+_7") (pintype "passive"))
    )
    (net (code "72") (name "/VREF-") (class "Default")
      (node (ref "C25") (pin "1") (pinfunction "1_1") (pintype "passive"))
      (node (ref "U7") (pin "11") (pinfunction "VREF-/VeREF-_11") (pintype "passive"))
    )
    (net (code "73") (name "/VeREF+") (class "Default")
      (node (ref "C24") (pin "1") (pinfunction "1_1") (pintype "passive"))
      (node (ref "U7") (pin "10") (pinfunction "VeREF+_10") (pintype "passive"))
    )
    (net (code "74") (name "BAT") (class "Default")
      (node (ref "C2") (pin "2") (pinfunction "2_2") (pintype "passive"))
      (node (ref "J1") (pin "2") (pinfunction "2_2") (pintype "passive"))
      (node (ref "S1") (pin "1") (pinfunction "1_1") (pintype "passive"))
      (node (ref "U2") (pin "3") (pinfunction "BAT_3") (pintype "passive"))
    )
    (net (code "75") (name "GND") (class "Default")
      (node (ref "C1") (pin "2") (pinfunction "2_2") (pintype "passive"))
      (node (ref "C10") (pin "2") (pinfunction "2_2") (pintype "passive"))
      (node (ref "C11") (pin "1") (pinfunction "1_1") (pintype "passive"))
      (node (ref "C12") (pin "2") (pinfunction "2_2") (pintype "passive"))
      (node (ref "C13") (pin "1") (pinfunction "1_1") (pintype "passive"))
      (node (ref "C14") (pin "2") (pinfunction "2_2") (pintype "passive"))
      (node (ref "C15") (pin "2") (pinfunction "2_2") (pintype "passive"))
      (node (ref "C16") (pin "2") (pinfunction "2_2") (pintype "passive"))
      (node (ref "C17") (pin "2") (pinfunction "2_2") (pintype "passive"))
      (node (ref "C18") (pin "2") (pinfunction "2_2") (pintype "passive"))
      (node (ref "C19") (pin "1") (pinfunction "1_1") (pintype "passive"))
      (node (ref "C2") (pin "1") (pinfunction "1_1") (pintype "passive"))
      (node (ref "C20") (pin "1") (pinfunction "1_1") (pintype "passive"))
      (node (ref "C21") (pin "1") (pinfunction "1_1") (pintype "passive"))
      (node (ref "C22") (pin "2") (pinfunction "2_2") (pintype "passive"))
      (node (ref "C23") (pin "2") (pinfunction "2_2") (pintype "passive"))
      (node (ref "C24") (pin "2") (pinfunction "2_2") (pintype "passive"))
      (node (ref "C25") (pin "2") (pinfunction "2_2") (pintype "passive"))
      (node (ref "C26") (pin "1") (pinfunction "1_1") (pintype "passive"))
      (node (ref "C27") (pin "1") (pinfunction "1_1") (pintype "passive"))
      (node (ref "C28") (pin "2") (pinfunction "2_2") (pintype "passive"))
      (node (ref "C29") (pin "2") (pinfunction "2_2") (pintype "passive"))
      (node (ref "C3") (pin "2") (pinfunction "2_2") (pintype "passive"))
      (node (ref "C30") (pin "1") (pinfunction "1_1") (pintype "passive"))
      (node (ref "C31") (pin "1") (pinfunction "1_1") (pintype "passive"))
      (node (ref "C4") (pin "1") (pinfunction "1_1") (pintype "passive"))
      (node (ref "C5") (pin "1") (pinfunction "1_1") (pintype "passive"))
      (node (ref "C6") (pin "1") (pinfunction "1_1") (pintype "passive"))
      (node (ref "C7") (pin "2") (pinfunction "2_2") (pintype "passive"))
      (node (ref "C8") (pin "2") (pinfunction "2_2") (pintype "passive"))
      (node (ref "C9") (pin "2") (pinfunction "2_2") (pintype "passive"))
      (node (ref "D4") (pin "K") (pinfunction "2_K") (pintype "passive"))
      (node (ref "J1") (pin "1") (pinfunction "1_1") (pintype "passive"))
      (node (ref "J2") (pin "1") (pinfunction "1_1") (pintype "passive"))
      (node (ref "J4") (pin "2") (pinfunction "2_2") (pintype "passive"))
      (node (ref "J4") (pin "5") (pinfunction "5_5") (pintype "passive"))
      (node (ref "J5") (pin "2") (pinfunction "2_2") (pintype "passive"))
      (node (ref "J5") (pin "5") (pinfunction "5_5") (pintype "passive"))
      (node (ref "JP1") (pin "1") (pinfunction "1_1") (pintype "passive"))
      (node (ref "JP1") (pin "23") (pinfunction "23_23") (pintype "passive"))
      (node (ref "JP1") (pin "24") (pinfunction "24_24") (pintype "passive"))
      (node (ref "JP2") (pin "4") (pinfunction "4_4") (pintype "passive"))
      (node (ref "JP2") (pin "6") (pinfunction "6_6") (pintype "passive"))
      (node (ref "JP3") (pin "8") (pinfunction "8_8") (pintype "passive"))
      (node (ref "JP4") (pin "4") (pinfunction "4_4") (pintype "passive"))
      (node (ref "JP4") (pin "6") (pinfunction "6_6") (pintype "passive"))
      (node (ref "JP5") (pin "8") (pinfunction "8_8") (pintype "passive"))
      (node (ref "JP6") (pin "2") (pinfunction "2_2") (pintype "passive"))
      (node (ref "JP6") (pin "5") (pinfunction "5_5") (pintype "passive"))
      (node (ref "JP6") (pin "8") (pinfunction "8_8") (pintype "passive"))
      (node (ref "K1") (pin "1") (pinfunction "1_1") (pintype "passive"))
      (node (ref "P1") (pin "4") (pinfunction "GND_4") (pintype "power_in"))
      (node (ref "P2") (pin "9") (pinfunction "9_9") (pintype "passive"))
      (node (ref "Q1") (pin "2") (pinfunction "E_2") (pintype "passive"))
      (node (ref "Q2") (pin "2") (pinfunction "E_2") (pintype "passive"))
      (node (ref "Q5") (pin "2") (pinfunction "E_2") (pintype "passive"))
      (node (ref "Q6") (pin "2") (pinfunction "E_2") (pintype "passive"))
      (node (ref "Q7") (pin "2") (pinfunction "E_2") (pintype "passive"))
      (node (ref "Q8") (pin "2") (pinfunction "E_2") (pintype "passive"))
      (node (ref "R23") (pin "1") (pinfunction "1_1") (pintype "passive"))
      (node (ref "R24") (pin "1") (pinfunction "1_1") (pintype "passive"))
      (node (ref "R29") (pin "2") (pinfunction "2_2") (pintype "passive"))
      (node (ref "R7") (pin "1") (pinfunction "1_1") (pintype "passive"))
      (node (ref "R9") (pin "2") (pinfunction "2_2") (pintype "passive"))
      (node (ref "SD1") (pin "10") (pinfunction "COM_10") (pintype "passive"))
      (node (ref "SD1") (pin "11") (pinfunction "COM_11") (pintype "passive"))
      (node (ref "SD1") (pin "12") (pinfunction "COM_12") (pintype "passive"))
      (node (ref "SD1") (pin "6") (pinfunction "VSS_6") (pintype "passive"))
      (node (ref "U1") (pin "11") (pinfunction "EPAD_11") (pintype "passive"))
      (node (ref "U1") (pin "3") (pinfunction "PGND_3") (pintype "passive"))
      (node (ref "U1") (pin "9") (pinfunction "GND_9") (pintype "passive"))
      (node (ref "U2") (pin "2") (pinfunction "GND_2") (pintype "passive"))
      (node (ref "U3") (pin "2") (pinfunction "GND_2") (pintype "passive"))
      (node (ref "U4") (pin "2") (pinfunction "GND_2") (pintype "passive"))
      (node (ref "U4") (pin "4") (pinfunction "GND_4") (pintype "passive"))
      (node (ref "U4") (pin "5") (pinfunction "GND_5") (pintype "passive"))
      (node (ref "U5") (pin "10") (pinfunction "NC_10") (pintype "passive"))
      (node (ref "U5") (pin "11") (pinfunction "NC_11") (pintype "passive"))
      (node (ref "U5") (pin "12") (pinfunction "NC_12") (pintype "passive"))
      (node (ref "U5") (pin "5") (pinfunction "NC_5") (pintype "passive"))
      (node (ref "U5") (pin "6") (pinfunction "NC_6") (pintype "passive"))
      (node (ref "U5") (pin "7") (pinfunction "NC_7") (pintype "passive"))
      (node (ref "U5") (pin "8") (pinfunction "NC_8") (pintype "passive"))
      (node (ref "U5") (pin "9") (pinfunction "NC_9") (pintype "passive"))
      (node (ref "U6") (pin "1") (pinfunction "A0_1") (pintype "passive"))
      (node (ref "U6") (pin "2") (pinfunction "A1_2") (pintype "passive"))
      (node (ref "U6") (pin "3") (pinfunction "A2_3") (pintype "passive"))
      (node (ref "U6") (pin "4") (pinfunction "GND_4") (pintype "passive"))
      (node (ref "U6") (pin "7") (pinfunction "WP_7") (pintype "passive"))
      (node (ref "U7") (pin "62") (pinfunction "AVss_62") (pintype "passive"))
      (node (ref "U7") (pin "63") (pinfunction "DVss_63") (pintype "passive"))
      (node (ref "U8") (pin "18") (pinfunction "GND_18") (pintype "passive"))
      (node (ref "U8") (pin "21") (pinfunction "GND_21") (pintype "passive"))
      (node (ref "U8") (pin "22") (pinfunction "GP0_22") (pintype "passive"))
      (node (ref "U8") (pin "23") (pinfunction "GP1_23") (pintype "passive"))
      (node (ref "U8") (pin "25") (pinfunction "GND_A_25") (pintype "passive"))
      (node (ref "U8") (pin "26") (pinfunction "PLL_TEST_26") (pintype "passive"))
      (node (ref "U8") (pin "7") (pinfunction "GND_7") (pintype "passive"))
      (node (ref "U9") (pin "12") (pinfunction "GND_12") (pintype "passive"))
    )
    (net (code "76") (name "Net-(C30-Pad2)") (class "Default")
      (node (ref "C30") (pin "2") (pinfunction "2_2") (pintype "passive"))
      (node (ref "R35") (pin "2") (pinfunction "2_2") (pintype "passive"))
      (node (ref "U8") (pin "17") (pinfunction "VDD_17") (pintype "passive"))
    )
    (net (code "77") (name "Net-(D1-2)") (class "Default")
      (node (ref "D1") (pin "K") (pinfunction "2_K") (pintype "passive"))
      (node (ref "U2") (pin "1") (pinfunction "~{CHRG}_1") (pintype "passive"))
    )
    (net (code "78") (name "Net-(D2-2)") (class "Default")
      (node (ref "D2") (pin "K") (pinfunction "2_K") (pintype "passive"))
      (node (ref "U2") (pin "5") (pinfunction "~{STDBY}_5") (pintype "passive"))
    )
    (net (code "79") (name "Net-(D3-A)") (class "Default")
      (node (ref "D3") (pin "1") (pinfunction "A_1") (pintype "passive"))
      (node (ref "L2") (pin "2") (pinfunction "2_2") (pintype "passive"))
      (node (ref "U3") (pin "1") (pinfunction "LX_1") (pintype "passive"))
    )
    (net (code "80") (name "Net-(D4-1)") (class "Default")
      (node (ref "D4") (pin "A") (pinfunction "1_A") (pintype "passive"))
      (node (ref "R25") (pin "1") (pinfunction "1_1") (pintype "passive"))
    )
    (net (code "81") (name "Net-(D5-A)") (class "Default")
      (node (ref "C15") (pin "1") (pinfunction "1_1") (pintype "passive"))
      (node (ref "D5") (pin "1") (pinfunction "A_1") (pintype "passive"))
      (node (ref "K1") (pin "2") (pinfunction "2_2") (pintype "passive"))
      (node (ref "R26") (pin "1") (pinfunction "1_1") (pintype "passive"))
    )
    (net (code "82") (name "Net-(Q1-B)") (class "Default")
      (node (ref "Q1") (pin "1") (pinfunction "B_1") (pintype "passive"))
      (node (ref "R5") (pin "2") (pinfunction "2_2") (pintype "passive"))
    )
    (net (code "83") (name "Net-(Q1-C)") (class "Default")
      (node (ref "Q1") (pin "3") (pinfunction "C_3") (pintype "passive"))
      (node (ref "R1") (pin "2") (pinfunction "2_2") (pintype "passive"))
      (node (ref "R3") (pin "2") (pinfunction "2_2") (pintype "passive"))
    )
    (net (code "84") (name "Net-(Q2-B)") (class "Default")
      (node (ref "Q2") (pin "1") (pinfunction "B_1") (pintype "passive"))
      (node (ref "R6") (pin "2") (pinfunction "2_2") (pintype "passive"))
    )
    (net (code "85") (name "Net-(Q2-C)") (class "Default")
      (node (ref "Q2") (pin "3") (pinfunction "C_3") (pintype "passive"))
      (node (ref "R2") (pin "2") (pinfunction "2_2") (pintype "passive"))
      (node (ref "R4") (pin "2") (pinfunction "2_2") (pintype "passive"))
    )
    (net (code "86") (name "Net-(Q3-G)") (class "Default")
      (node (ref "Q3") (pin "1") (pinfunction "G_1") (pintype "input"))
      (node (ref "R1") (pin "1") (pinfunction "1_1") (pintype "passive"))
    )
    (net (code "87") (name "Net-(Q4-G)") (class "Default")
      (node (ref "Q4") (pin "1") (pinfunction "G_1") (pintype "input"))
      (node (ref "R2") (pin "1") (pinfunction "1_1") (pintype "passive"))
    )
    (net (code "88") (name "Net-(Q5-B)") (class "Default")
      (node (ref "Q5") (pin "1") (pinfunction "B_1") (pintype "passive"))
      (node (ref "R19") (pin "2") (pinfunction "2_2") (pintype "passive"))
    )
    (net (code "89") (name "Net-(Q5-C)") (class "Default")
      (node (ref "Q5") (pin "3") (pinfunction "C_3") (pintype "passive"))
      (node (ref "R10") (pin "2") (pinfunction "2_2") (pintype "passive"))
      (node (ref "R15") (pin "2") (pinfunction "2_2") (pintype "passive"))
    )
    (net (code "90") (name "Net-(Q6-B)") (class "Default")
      (node (ref "Q6") (pin "1") (pinfunction "B_1") (pintype "passive"))
      (node (ref "R20") (pin "2") (pinfunction "2_2") (pintype "passive"))
    )
    (net (code "91") (name "Net-(Q6-C)") (class "Default")
      (node (ref "Q6") (pin "3") (pinfunction "C_3") (pintype "passive"))
      (node (ref "R11") (pin "2") (pinfunction "2_2") (pintype "passive"))
      (node (ref "R16") (pin "2") (pinfunction "2_2") (pintype "passive"))
    )
    (net (code "92") (name "Net-(Q7-B)") (class "Default")
      (node (ref "Q7") (pin "1") (pinfunction "B_1") (pintype "passive"))
      (node (ref "R21") (pin "2") (pinfunction "2_2") (pintype "passive"))
    )
    (net (code "93") (name "Net-(Q7-C)") (class "Default")
      (node (ref "Q7") (pin "3") (pinfunction "C_3") (pintype "passive"))
      (node (ref "R12") (pin "2") (pinfunction "2_2") (pintype "passive"))
      (node (ref "R17") (pin "2") (pinfunction "2_2") (pintype "passive"))
    )
    (net (code "94") (name "Net-(Q8-B)") (class "Default")
      (node (ref "Q8") (pin "1") (pinfunction "B_1") (pintype "passive"))
      (node (ref "R22") (pin "2") (pinfunction "2_2") (pintype "passive"))
    )
    (net (code "95") (name "Net-(Q8-C)") (class "Default")
      (node (ref "Q8") (pin "3") (pinfunction "C_3") (pintype "passive"))
      (node (ref "R13") (pin "2") (pinfunction "2_2") (pintype "passive"))
      (node (ref "R18") (pin "2") (pinfunction "2_2") (pintype "passive"))
    )
    (net (code "96") (name "Net-(Q9-G)") (class "Default")
      (node (ref "Q9") (pin "1") (pinfunction "G_1") (pintype "input"))
      (node (ref "R10") (pin "1") (pinfunction "1_1") (pintype "passive"))
    )
    (net (code "97") (name "Net-(Q10-G)") (class "Default")
      (node (ref "Q10") (pin "1") (pinfunction "G_1") (pintype "input"))
      (node (ref "R11") (pin "1") (pinfunction "1_1") (pintype "passive"))
    )
    (net (code "98") (name "Net-(Q11-G)") (class "Default")
      (node (ref "Q11") (pin "1") (pinfunction "G_1") (pintype "input"))
      (node (ref "R12") (pin "1") (pinfunction "1_1") (pintype "passive"))
    )
    (net (code "99") (name "Net-(Q12-G)") (class "Default")
      (node (ref "Q12") (pin "1") (pinfunction "G_1") (pintype "input"))
      (node (ref "R13") (pin "1") (pinfunction "1_1") (pintype "passive"))
    )
    (net (code "100") (name "Net-(SD1-DAT1)") (class "Default")
      (node (ref "R42") (pin "2") (pinfunction "2_2") (pintype "passive"))
      (node (ref "SD1") (pin "8") (pinfunction "DAT1_8") (pintype "passive"))
    )
    (net (code "101") (name "Net-(SD1-DAT2)") (class "Default")
      (node (ref "R41") (pin "2") (pinfunction "2_2") (pintype "passive"))
      (node (ref "SD1") (pin "1") (pinfunction "DAT2_1") (pintype "passive"))
    )
    (net (code "102") (name "Net-(U1-L1)") (class "Default")
      (node (ref "L1") (pin "2") (pinfunction "2_2") (pintype "passive"))
      (node (ref "U1") (pin "4") (pinfunction "L1_4") (pintype "passive"))
    )
    (net (code "103") (name "Net-(U1-L2)") (class "Default")
      (node (ref "L1") (pin "1") (pinfunction "1_1") (pintype "passive"))
      (node (ref "U1") (pin "2") (pinfunction "L2_2") (pintype "passive"))
    )
    (net (code "104") (name "Net-(U2-PROG)") (class "Default")
      (node (ref "R7") (pin "2") (pinfunction "2_2") (pintype "passive"))
      (node (ref "U2") (pin "6") (pinfunction "PROG_6") (pintype "passive"))
    )
    (net (code "105") (name "Net-(U3-FB)") (class "Default")
      (node (ref "R14") (pin "1") (pinfunction "1_1") (pintype "passive"))
      (node (ref "R24") (pin "2") (pinfunction "2_2") (pintype "passive"))
      (node (ref "U3") (pin "3") (pinfunction "FB_3") (pintype "passive"))
    )
    (net (code "106") (name "Net-(U3-OC)") (class "Default")
      (node (ref "R23") (pin "2") (pinfunction "2_2") (pintype "passive"))
      (node (ref "U3") (pin "6") (pinfunction "OC_6") (pintype "passive"))
    )
    (net (code "107") (name "Net-(U4-SDO)") (class "Default")
      (node (ref "R29") (pin "1") (pinfunction "1_1") (pintype "passive"))
      (node (ref "U4") (pin "12") (pinfunction "SDO_12") (pintype "passive"))
    )
    (net (code "108") (name "Net-(U4-Vs)") (class "Default")
      (node (ref "R27") (pin "2") (pinfunction "2_2") (pintype "passive"))
      (node (ref "U4") (pin "6") (pinfunction "Vs_6") (pintype "passive"))
    )
    (net (code "109") (name "Net-(U4-~{C}S)") (class "Default")
      (node (ref "R30") (pin "2") (pinfunction "2_2") (pintype "passive"))
      (node (ref "U4") (pin "7") (pinfunction "~{C}S_7") (pintype "passive"))
    )
    (net (code "110") (name "Net-(U5-32KHz)") (class "Default")
      (node (ref "R28") (pin "1") (pinfunction "1_1") (pintype "passive"))
      (node (ref "U5") (pin "1") (pinfunction "32KHz_1") (pintype "passive"))
    )
    (net (code "111") (name "Net-(U7-XIN)") (class "Default")
      (node (ref "C19") (pin "2") (pinfunction "2_2") (pintype "passive"))
      (node (ref "U7") (pin "8") (pinfunction "XIN_8") (pintype "passive"))
      (node (ref "XT2") (pin "2") (pinfunction "2_2") (pintype "passive"))
    )
    (net (code "112") (name "Net-(U7-XOUT{slash}TCLK)") (class "Default")
      (node (ref "C21") (pin "2") (pinfunction "2_2") (pintype "passive"))
      (node (ref "U7") (pin "9") (pinfunction "XOUT/TCLK_9") (pintype "passive"))
      (node (ref "XT2") (pin "1") (pinfunction "1_1") (pintype "passive"))
    )
    (net (code "113") (name "Net-(U7-XT2IN)") (class "Default")
      (node (ref "C13") (pin "2") (pinfunction "2_2") (pintype "passive"))
      (node (ref "U7") (pin "53") (pinfunction "XT2IN_53") (pintype "passive"))
      (node (ref "XT1") (pin "2") (pinfunction "2_2") (pintype "passive"))
    )
    (net (code "114") (name "Net-(U7-XT2OUT)") (class "Default")
      (node (ref "C11") (pin "2") (pinfunction "2_2") (pintype "passive"))
      (node (ref "U7") (pin "52") (pinfunction "XT2OUT_52") (pintype "passive"))
      (node (ref "XT1") (pin "1") (pinfunction "1_1") (pintype "passive"))
    )
    (net (code "115") (name "Net-(U8-DM)") (class "Default")
      (node (ref "R38") (pin "2") (pinfunction "2_2") (pintype "passive"))
      (node (ref "U8") (pin "16") (pinfunction "DM_16") (pintype "passive"))
    )
    (net (code "116") (name "Net-(U8-DP)") (class "Default")
      (node (ref "R40") (pin "2") (pinfunction "2_2") (pintype "passive"))
      (node (ref "U8") (pin "15") (pinfunction "DP_15") (pintype "passive"))
    )
    (net (code "117") (name "Net-(U8-EECLK)") (class "Default")
      (node (ref "R37") (pin "1") (pinfunction "1_1") (pintype "passive"))
      (node (ref "U8") (pin "13") (pinfunction "EECLK_13") (pintype "passive"))
    )
    (net (code "118") (name "Net-(U8-EE_DATA)") (class "Default")
      (node (ref "R39") (pin "1") (pinfunction "1_1") (pintype "passive"))
      (node (ref "U8") (pin "14") (pinfunction "EE_DATA_14") (pintype "passive"))
    )
    (net (code "119") (name "Net-(U8-OSC1)") (class "Default")
      (node (ref "C28") (pin "1") (pinfunction "1_1") (pintype "passive"))
      (node (ref "U8") (pin "27") (pinfunction "OSC1_27") (pintype "passive"))
      (node (ref "XT4") (pin "1") (pinfunction "1_1") (pintype "passive"))
    )
    (net (code "120") (name "Net-(U8-OSC2)") (class "Default")
      (node (ref "C22") (pin "1") (pinfunction "1_1") (pintype "passive"))
      (node (ref "U8") (pin "28") (pinfunction "OSC2_28") (pintype "passive"))
      (node (ref "XT4") (pin "2") (pinfunction "2_2") (pintype "passive"))
    )
    (net (code "121") (name "Net-(U8-RXD)") (class "Default")
      (node (ref "R34") (pin "1") (pinfunction "1_1") (pintype "passive"))
      (node (ref "U8") (pin "5") (pinfunction "RXD_5") (pintype "passive"))
    )
    (net (code "122") (name "Net-(U8-TXD)") (class "Default")
      (node (ref "R33") (pin "1") (pinfunction "1_1") (pintype "passive"))
      (node (ref "U8") (pin "1") (pinfunction "TXD_1") (pintype "passive"))
    )
    (net (code "123") (name "Net-(U9-OSCI)") (class "Default")
      (node (ref "C23") (pin "1") (pinfunction "1_1") (pintype "passive"))
      (node (ref "U9") (pin "1") (pinfunction "OSCI_1") (pintype "passive"))
      (node (ref "XT3") (pin "2") (pinfunction "2_2") (pintype "passive"))
    )
    (net (code "124") (name "Net-(U9-OSCO)") (class "Default")
      (node (ref "C26") (pin "2") (pinfunction "2_2") (pintype "passive"))
      (node (ref "U9") (pin "2") (pinfunction "OSCO_2") (pintype "passive"))
      (node (ref "XT3") (pin "1") (pinfunction "1_1") (pintype "passive"))
    )
    (net (code "125") (name "VBUS") (class "Default")
      (node (ref "C10") (pin "1") (pinfunction "1_1") (pintype "passive"))
      (node (ref "C4") (pin "2") (pinfunction "2_2") (pintype "passive"))
      (node (ref "C5") (pin "2") (pinfunction "2_2") (pintype "passive"))
      (node (ref "C9") (pin "1") (pinfunction "1_1") (pintype "passive"))
      (node (ref "J5") (pin "1") (pinfunction "1_1") (pintype "passive"))
      (node (ref "JP1") (pin "21") (pinfunction "21_21") (pintype "passive"))
      (node (ref "JP3") (pin "7") (pinfunction "7_7") (pintype "passive"))
      (node (ref "JP5") (pin "7") (pinfunction "7_7") (pintype "passive"))
      (node (ref "JP6") (pin "1") (pinfunction "1_1") (pintype "passive"))
      (node (ref "L2") (pin "1") (pinfunction "1_1") (pintype "passive"))
      (node (ref "R8") (pin "2") (pinfunction "2_2") (pintype "passive"))
      (node (ref "S1") (pin "2") (pinfunction "2_2") (pintype "passive"))
      (node (ref "U1") (pin "5") (pinfunction "VIN_5") (pintype "passive"))
      (node (ref "U1") (pin "6") (pinfunction "EN_6") (pintype "passive"))
      (node (ref "U1") (pin "7") (pinfunction "PS/SYNC_7") (pintype "passive"))
      (node (ref "U1") (pin "8") (pinfunction "VINA_8") (pintype "passive"))
      (node (ref "U3") (pin "4") (pinfunction "EN_4") (pintype "passive"))
      (node (ref "U3") (pin "5") (pinfunction "VCC_5") (pintype "passive"))
    )
    (net (code "126") (name "VCC_Base_3.3V") (class "Default")
      (node (ref "C1") (pin "1") (pinfunction "1_1") (pintype "passive"))
      (node (ref "C12") (pin "1") (pinfunction "1_1") (pintype "passive"))
      (node (ref "C14") (pin "1") (pinfunction "1_1") (pintype "passive"))
      (node (ref "C16") (pin "1") (pinfunction "1_1") (pintype "passive"))
      (node (ref "C17") (pin "1") (pinfunction "1_1") (pintype "passive"))
      (node (ref "C18") (pin "1") (pinfunction "1_1") (pintype "passive"))
      (node (ref "C27") (pin "2") (pinfunction "2_2") (pintype "passive"))
      (node (ref "C29") (pin "1") (pinfunction "1_1") (pintype "passive"))
      (node (ref "D5") (pin "2") (pinfunction "K_2") (pintype "passive"))
      (node (ref "Q10") (pin "2") (pinfunction "D_2") (pintype "input"))
      (node (ref "Q11") (pin "2") (pinfunction "D_2") (pintype "input"))
      (node (ref "Q3") (pin "2") (pinfunction "D_2") (pintype "input"))
      (node (ref "Q4") (pin "2") (pinfunction "D_2") (pintype "input"))
      (node (ref "R16") (pin "1") (pinfunction "1_1") (pintype "passive"))
      (node (ref "R17") (pin "1") (pinfunction "1_1") (pintype "passive"))
      (node (ref "R26") (pin "2") (pinfunction "2_2") (pintype "passive"))
      (node (ref "R27") (pin "1") (pinfunction "1_1") (pintype "passive"))
      (node (ref "R28") (pin "2") (pinfunction "2_2") (pintype "passive"))
      (node (ref "R3") (pin "1") (pinfunction "1_1") (pintype "passive"))
      (node (ref "R30") (pin "1") (pinfunction "1_1") (pintype "passive"))
      (node (ref "R31") (pin "2") (pinfunction "2_2") (pintype "passive"))
      (node (ref "R32") (pin "2") (pinfunction "2_2") (pintype "passive"))
      (node (ref "R36") (pin "1") (pinfunction "1_1") (pintype "passive"))
      (node (ref "R37") (pin "2") (pinfunction "2_2") (pintype "passive"))
      (node (ref "R39") (pin "2") (pinfunction "2_2") (pintype "passive"))
      (node (ref "R4") (pin "1") (pinfunction "1_1") (pintype "passive"))
      (node (ref "U1") (pin "1") (pinfunction "Vout_1") (pintype "passive"))
      (node (ref "U1") (pin "10") (pinfunction "FB_10") (pintype "passive"))
      (node (ref "U4") (pin "1") (pinfunction "Vdd_1") (pintype "passive"))
      (node (ref "U5") (pin "2") (pinfunction "VCC_2") (pintype "passive"))
      (node (ref "U6") (pin "8") (pinfunction "VCC_8") (pintype "passive"))
      (node (ref "U7") (pin "1") (pinfunction "DVCC_1") (pintype "passive"))
      (node (ref "U7") (pin "64") (pinfunction "AVcc_64") (pintype "passive"))
      (node (ref "U8") (pin "4") (pinfunction "VDD_4") (pintype "passive"))
      (node (ref "U9") (pin "24") (pinfunction "VDD_24") (pintype "passive"))
    )
    (net (code "127") (name "VCC_Base_5V") (class "Default")
      (node (ref "C7") (pin "1") (pinfunction "1_1") (pintype "passive"))
      (node (ref "C8") (pin "1") (pinfunction "1_1") (pintype "passive"))
      (node (ref "D3") (pin "2") (pinfunction "K_2") (pintype "passive"))
      (node (ref "Q12") (pin "2") (pinfunction "D_2") (pintype "input"))
      (node (ref "Q9") (pin "2") (pinfunction "D_2") (pintype "input"))
      (node (ref "R14") (pin "2") (pinfunction "2_2") (pintype "passive"))
      (node (ref "R15") (pin "1") (pinfunction "1_1") (pintype "passive"))
      (node (ref "R18") (pin "1") (pinfunction "1_1") (pintype "passive"))
      (node (ref "U8") (pin "19") (pinfunction "NC_19") (pintype "passive"))
      (node (ref "U8") (pin "20") (pinfunction "VDD_20") (pintype "passive"))
    )
    (net (code "128") (name "VCC_SD_3.3V") (class "Default")
      (node (ref "C31") (pin "2") (pinfunction "2_2") (pintype "passive"))
      (node (ref "Q10") (pin "3") (pinfunction "S_3") (pintype "input"))
      (node (ref "R41") (pin "1") (pinfunction "1_1") (pintype "passive"))
      (node (ref "R42") (pin "1") (pinfunction "1_1") (pintype "passive"))
      (node (ref "SD1") (pin "4") (pinfunction "VDD_4") (pintype "passive"))
    )
    (net (code "129") (name "VIN") (class "Default")
      (node (ref "C6") (pin "2") (pinfunction "2_2") (pintype "passive"))
      (node (ref "D1") (pin "A") (pinfunction "1_A") (pintype "passive"))
      (node (ref "D2") (pin "A") (pinfunction "1_A") (pintype "passive"))
      (node (ref "J2") (pin "2") (pinfunction "2_2") (pintype "passive"))
      (node (ref "P1") (pin "1") (pinfunction "VCC_1") (pintype "power_in"))
      (node (ref "U2") (pin "4") (pinfunction "VCC_4") (pintype "passive"))
    )
    (net (code "130") (name "unconnected-(HO1-A-Pad1)") (class "Default")
      (node (ref "HO1") (pin "1") (pinfunction "A_1") (pintype "passive"))
    )
    (net (code "131") (name "unconnected-(HO2-A-Pad1)") (class "Default")
      (node (ref "HO2") (pin "1") (pinfunction "A_1") (pintype "passive"))
    )
    (net (code "132") (name "unconnected-(HO3-A-Pad1)") (class "Default")
      (node (ref "HO3") (pin "1") (pinfunction "A_1") (pintype "passive"))
    )
    (net (code "133") (name "unconnected-(HO4-A-Pad1)") (class "Default")
      (node (ref "HO4") (pin "1") (pinfunction "A_1") (pintype "passive"))
    )
    (net (code "134") (name "unconnected-(P2-Pad2)") (class "Default")
      (node (ref "P2") (pin "2") (pinfunction "2_2") (pintype "passive"))
    )
    (net (code "135") (name "unconnected-(P2-Pad4)") (class "Default")
      (node (ref "P2") (pin "4") (pinfunction "4_4") (pintype "passive"))
    )
    (net (code "136") (name "unconnected-(P2-Pad6)") (class "Default")
      (node (ref "P2") (pin "6") (pinfunction "6_6") (pintype "passive"))
    )
    (net (code "137") (name "unconnected-(P2-Pad8)") (class "Default")
      (node (ref "P2") (pin "8") (pinfunction "8_8") (pintype "passive"))
    )
    (net (code "138") (name "unconnected-(P2-Pad10)") (class "Default")
      (node (ref "P2") (pin "10") (pinfunction "10_10") (pintype "passive"))
    )
    (net (code "139") (name "unconnected-(P2-Pad12)") (class "Default")
      (node (ref "P2") (pin "12") (pinfunction "12_12") (pintype "passive"))
    )
    (net (code "140") (name "unconnected-(P2-Pad13)") (class "Default")
      (node (ref "P2") (pin "13") (pinfunction "13_13") (pintype "passive"))
    )
    (net (code "141") (name "unconnected-(P2-Pad14)") (class "Default")
      (node (ref "P2") (pin "14") (pinfunction "14_14") (pintype "passive"))
    )
    (net (code "142") (name "unconnected-(S1-Pad3)") (class "Default")
      (node (ref "S1") (pin "3") (pinfunction "3_3") (pintype "passive"))
    )
    (net (code "143") (name "unconnected-(SD1-COM-Pad9)") (class "Default")
      (node (ref "SD1") (pin "9") (pinfunction "COM_9") (pintype "passive+no_connect"))
    )
    (net (code "144") (name "unconnected-(U4-INT1-Pad8)") (class "Default")
      (node (ref "U4") (pin "8") (pinfunction "INT1_8") (pintype "passive+no_connect"))
    )
    (net (code "145") (name "unconnected-(U4-INT2-Pad9)") (class "Default")
      (node (ref "U4") (pin "9") (pinfunction "INT2_9") (pintype "passive+no_connect"))
    )
    (net (code "146") (name "unconnected-(U4-NC-Pad10)") (class "Default")
      (node (ref "U4") (pin "10") (pinfunction "NC_10") (pintype "passive+no_connect"))
    )
    (net (code "147") (name "unconnected-(U4-NP-Pad3)") (class "Default")
      (node (ref "U4") (pin "3") (pinfunction "NP_3") (pintype "passive+no_connect"))
    )
    (net (code "148") (name "unconnected-(U4-NP-Pad11)") (class "Default")
      (node (ref "U4") (pin "11") (pinfunction "NP_11") (pintype "passive+no_connect"))
    )
    (net (code "149") (name "unconnected-(U5-GND-Pad13)") (class "Default")
      (node (ref "U5") (pin "13") (pinfunction "GND_13") (pintype "passive"))
    )
    (net (code "150") (name "unconnected-(U5-VBAT-Pad14)") (class "Default")
      (node (ref "U5") (pin "14") (pinfunction "VBAT_14") (pintype "passive"))
    )
    (net (code "151") (name "unconnected-(U5-~{IN}T-Pad3)") (class "Default")
      (node (ref "U5") (pin "3") (pinfunction "~{IN}T_3") (pintype "passive+no_connect"))
    )
    (net (code "152") (name "unconnected-(U8-CTS_N-Pad11)") (class "Default")
      (node (ref "U8") (pin "11") (pinfunction "CTS_N_11") (pintype "passive"))
    )
    (net (code "153") (name "unconnected-(U8-DCD_N-Pad10)") (class "Default")
      (node (ref "U8") (pin "10") (pinfunction "DCD_N_10") (pintype "passive"))
    )
    (net (code "154") (name "unconnected-(U8-DSR_N-Pad9)") (class "Default")
      (node (ref "U8") (pin "9") (pinfunction "DSR_N_9") (pintype "passive"))
    )
    (net (code "155") (name "unconnected-(U8-DTR_N-Pad2)") (class "Default")
      (node (ref "U8") (pin "2") (pinfunction "DTR_N_2") (pintype "passive"))
    )
    (net (code "156") (name "unconnected-(U8-NC-Pad8)") (class "Default")
      (node (ref "U8") (pin "8") (pinfunction "NC_8") (pintype "passive"))
    )
    (net (code "157") (name "unconnected-(U8-NC-Pad24)") (class "Default")
      (node (ref "U8") (pin "24") (pinfunction "NC_24") (pintype "passive"))
    )
    (net (code "158") (name "unconnected-(U8-RI_N-Pad6)") (class "Default")
      (node (ref "U8") (pin "6") (pinfunction "RI_N_6") (pintype "passive"))
    )
    (net (code "159") (name "unconnected-(U8-RTS-Pad3)") (class "Default")
      (node (ref "U8") (pin "3") (pinfunction "RTS_3") (pintype "passive"))
    )
    (net (code "160") (name "unconnected-(U8-SHTD_N-Pad12)") (class "Default")
      (node (ref "U8") (pin "12") (pinfunction "SHTD_N_12") (pintype "passive"))
    )
  )
)
